# AFE4220.net
KiCad netlist of a schematic drawn in Altium Designer
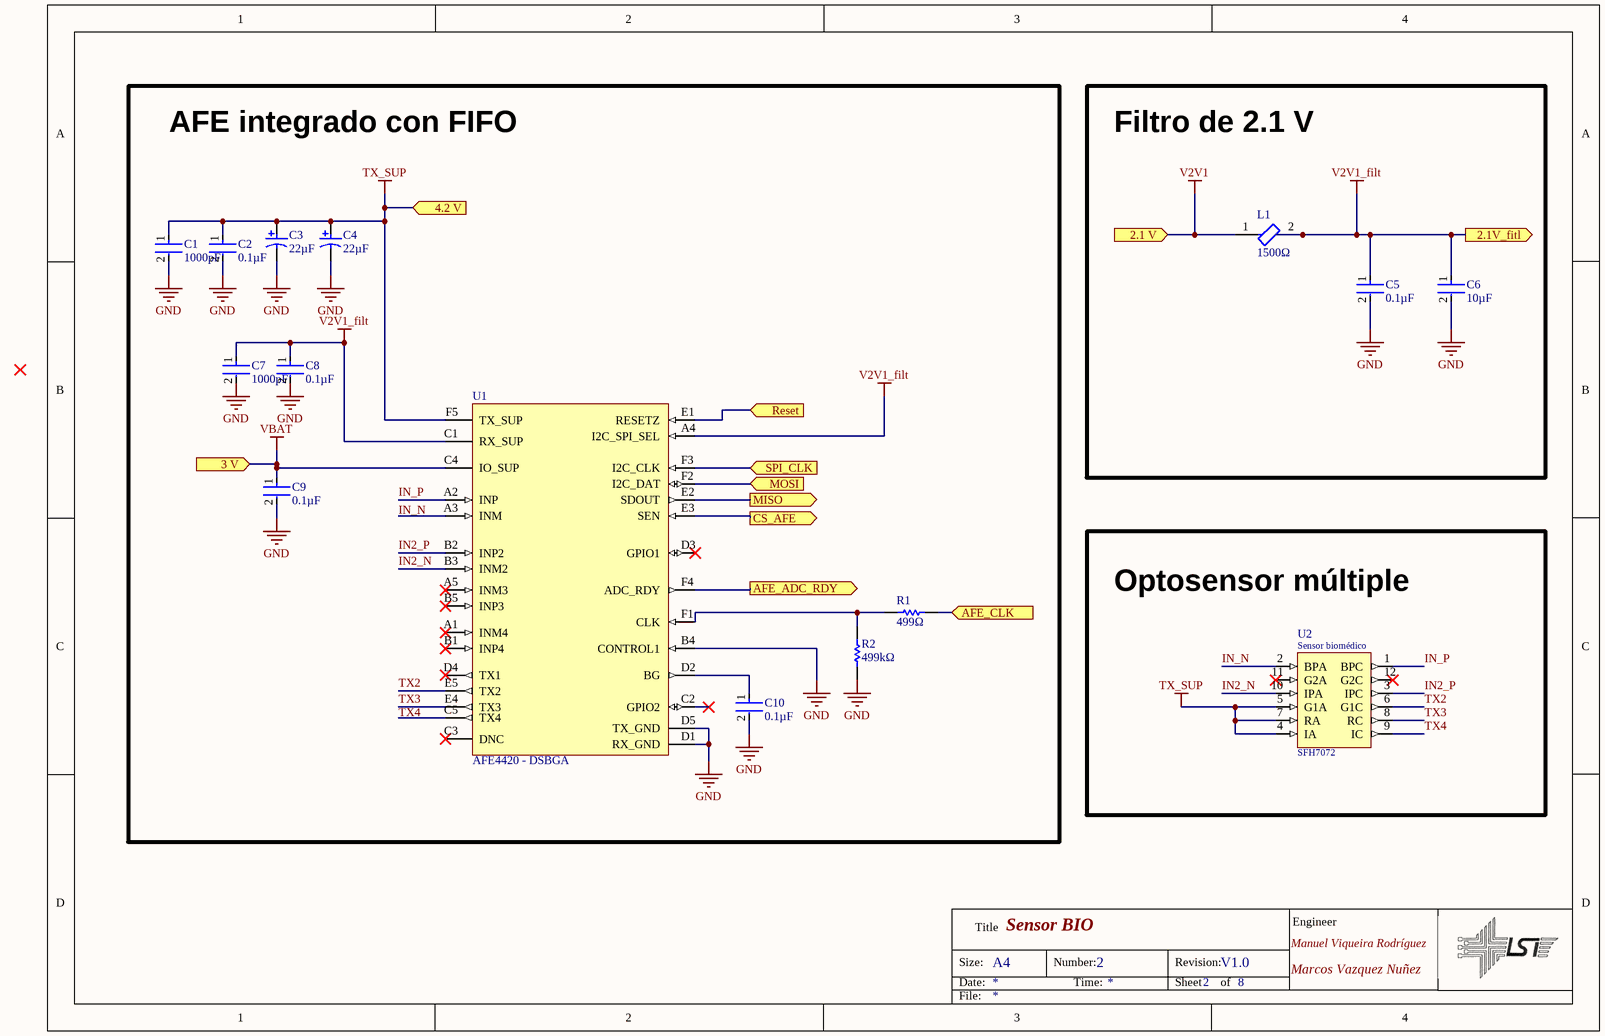
[diagram p0: AFE4220.SchDoc]

(export (version "E")
  (design (tool "Eeschema 10.0.6"))
  (components
    (comp (ref "C1")
      (value "1000pF")
      (footprint "FP-CL10-IPC_B")
      (description "Cap Ceramic 10uF 10V X5R ±10% Pad SMD 0603 +85°C T/R")
      (fields (field (name "TOLERANCE") "10%"))
      (libsource (lib "Altium Content Vault") (part "b4654b650e69147ec39a6b967a45e02"))
    )
    (comp (ref "C2")
      (value "0.1µF")
      (footprint "FP-CL10-IPC_B")
      (description "Cap Ceramic 10uF 10V X5R ±10% Pad SMD 0603 +85°C T/R")
      (fields (field (name "TOLERANCE") "10%"))
      (libsource (lib "Altium Content Vault") (part "b4654b650e69147ec39a6b967a45e02"))
    )
    (comp (ref "C3")
      (value "22µF")
      (footprint "NIC-CAPA2-4X5.8_V")
      (fields (field (name "MANUFACTURER") "Nichicon") (field (name "PARTNUMBER") "UUD1A220MCL1GS"))
      (libsource (lib "Altium Content Vault") (part "NIC-CAP-P-2"))
    )
    (comp (ref "C4")
      (value "22µF")
      (footprint "NIC-CAPA2-4X5.8_V")
      (fields (field (name "MANUFACTURER") "Nichicon") (field (name "PARTNUMBER") "UUD1A220MCL1GS"))
      (libsource (lib "Altium Content Vault") (part "NIC-CAP-P-2"))
    )
    (comp (ref "C5")
      (value "0.1µF")
      (footprint "FP-CL10-IPC_B")
      (description "Cap Ceramic 10uF 10V X5R ±10% Pad SMD 0603 +85°C T/R")
      (fields (field (name "TOLERANCE") "10%"))
      (libsource (lib "Altium Content Vault") (part "b4654b650e69147ec39a6b967a45e02"))
    )
    (comp (ref "C6")
      (value "10µF")
      (footprint "FP-CL10-IPC_B")
      (description "Cap Ceramic 10uF 10V X5R ±10% Pad SMD 0603 +85°C T/R")
      (fields (field (name "TOLERANCE") "10%"))
      (libsource (lib "Altium Content Vault") (part "b4654b650e69147ec39a6b967a45e02"))
    )
    (comp (ref "C7")
      (value "1000pF")
      (footprint "FP-CL10-IPC_B")
      (description "Cap Ceramic 10uF 10V X5R ±10% Pad SMD 0603 +85°C T/R")
      (fields (field (name "TOLERANCE") "10%"))
      (libsource (lib "Altium Content Vault") (part "b4654b650e69147ec39a6b967a45e02"))
    )
    (comp (ref "C8")
      (value "0.1µF")
      (footprint "FP-CL10-IPC_B")
      (description "Cap Ceramic 10uF 10V X5R ±10% Pad SMD 0603 +85°C T/R")
      (fields (field (name "TOLERANCE") "10%"))
      (libsource (lib "Altium Content Vault") (part "b4654b650e69147ec39a6b967a45e02"))
    )
    (comp (ref "C9")
      (value "0.1µF")
      (footprint "FP-CL10-IPC_B")
      (description "Cap Ceramic 10uF 10V X5R ±10% Pad SMD 0603 +85°C T/R")
      (fields (field (name "TOLERANCE") "10%"))
      (libsource (lib "Altium Content Vault") (part "b4654b650e69147ec39a6b967a45e02"))
    )
    (comp (ref "C10")
      (value "0.1µF")
      (footprint "FP-CL10-IPC_B")
      (description "Cap Ceramic 10uF 10V X5R ±10% Pad SMD 0603 +85°C T/R")
      (fields (field (name "TOLERANCE") "10%"))
      (libsource (lib "Altium Content Vault") (part "b4654b650e69147ec39a6b967a45e02"))
    )
    (comp (ref "L1")
      (value "1500Ω")
      (footprint "FP-BLM18-0_15-t0_8-IPC_C")
      (description "Chip Ferrite Bead, 0603, 1500Ω @ 100MHz, 0.5Ω, 25%, 500mA")
      (fields (field (name "TOLERANCE") "25%"))
      (libsource (lib "Altium Content Vault") (part "5f30dd21d616792df468990f7003faa"))
    )
    (comp (ref "R1")
      (value "499Ω")
      (footprint "RESC0603X28X15ML05T05")
      (fields (field (name "MANUFACTURER") "Vishay Dale") (field (name "PART NUMBER") "CRCW020120K0JNED"))
      (libsource (lib "Altium Content Vault") (part "RES"))
    )
    (comp (ref "R2")
      (value "499kΩ")
      (footprint "RESC0603X28X15ML05T05")
      (fields (field (name "MANUFACTURER") "Vishay Dale") (field (name "PART NUMBER") "CRCW020120K0JNED"))
      (libsource (lib "Altium Content Vault") (part "RES"))
    )
    (comp (ref "U1")
      (value "AFE4420 - DSBGA")
      (footprint "AFE4420 - DSBGA")
      (libsource (lib "DEOP2021") (part "AFE4420 - DSBGA"))
    )
    (comp (ref "U2")
      (value "~")
      (footprint "SFH7072")
      (description "Sensor biométrico")
      (libsource (lib "DEOP2021") (part "SFH7072"))
    )
  )
  (nets
    (net (code "1") (name "/AFE_ADC_RDY") (class "Default")
      (node (ref "U1") (pin "F4") (pinfunction "ADC_RDY_F4") (pintype "output"))
    )
    (net (code "2") (name "/AFE_CLK") (class "Default")
      (node (ref "R1") (pin "2") (pinfunction "2_2") (pintype "passive"))
    )
    (net (code "3") (name "/CS_AFE") (class "Default")
      (node (ref "U1") (pin "E3") (pinfunction "SEN_E3") (pintype "input"))
    )
    (net (code "4") (name "/IN2_N") (class "Default")
      (node (ref "U1") (pin "B3") (pinfunction "INM2_B3") (pintype "input"))
      (node (ref "U2") (pin "10") (pinfunction "IPA_10") (pintype "input"))
    )
    (net (code "5") (name "/IN2_P") (class "Default")
      (node (ref "U1") (pin "B2") (pinfunction "INP2_B2") (pintype "input"))
      (node (ref "U2") (pin "3") (pinfunction "IPC_3") (pintype "output"))
    )
    (net (code "6") (name "/IN_N") (class "Default")
      (node (ref "U2") (pin "2") (pinfunction "BPA_2") (pintype "input"))
    )
    (net (code "7") (name "/IN_P") (class "Default")
      (node (ref "U1") (pin "A2") (pinfunction "INP_A2") (pintype "input"))
      (node (ref "U2") (pin "1") (pinfunction "BPC_1") (pintype "output"))
    )
    (net (code "8") (name "/MISO") (class "Default")
      (node (ref "U1") (pin "E2") (pinfunction "SDOUT_E2") (pintype "output"))
    )
    (net (code "9") (name "/MOSI") (class "Default")
      (node (ref "U1") (pin "F2") (pinfunction "I2C_DAT_F2") (pintype "bidirectional"))
    )
    (net (code "10") (name "/Reset") (class "Default")
      (node (ref "U1") (pin "E1") (pinfunction "RESETZ_E1") (pintype "input"))
    )
    (net (code "11") (name "/SPI_CLK") (class "Default")
      (node (ref "U1") (pin "F3") (pinfunction "I2C_CLK_F3") (pintype "input"))
    )
    (net (code "12") (name "/TX2") (class "Default")
      (node (ref "U1") (pin "E5") (pinfunction "TX2_E5") (pintype "output"))
      (node (ref "U2") (pin "6") (pinfunction "G1C_6") (pintype "output"))
    )
    (net (code "13") (name "/TX3") (class "Default")
      (node (ref "U1") (pin "E4") (pinfunction "TX3_E4") (pintype "output"))
      (node (ref "U2") (pin "8") (pinfunction "RC_8") (pintype "output"))
    )
    (net (code "14") (name "/TX4") (class "Default")
      (node (ref "U2") (pin "9") (pinfunction "IC_9") (pintype "output"))
    )
    (net (code "15") (name "GND") (class "Default")
      (node (ref "C1") (pin "2") (pinfunction "2_2") (pintype "passive"))
      (node (ref "C10") (pin "2") (pinfunction "2_2") (pintype "passive"))
      (node (ref "C2") (pin "2") (pinfunction "2_2") (pintype "passive"))
      (node (ref "C3") (pin "2") (pinfunction "2_2") (pintype "passive"))
      (node (ref "C4") (pin "2") (pinfunction "2_2") (pintype "passive"))
      (node (ref "C5") (pin "2") (pinfunction "2_2") (pintype "passive"))
      (node (ref "C6") (pin "2") (pinfunction "2_2") (pintype "passive"))
      (node (ref "C7") (pin "2") (pinfunction "2_2") (pintype "passive"))
      (node (ref "C8") (pin "2") (pinfunction "2_2") (pintype "passive"))
      (node (ref "C9") (pin "2") (pinfunction "2_2") (pintype "passive"))
      (node (ref "R2") (pin "1") (pinfunction "1_1") (pintype "passive"))
      (node (ref "U1") (pin "B4") (pinfunction "CONTROL1_B4") (pintype "input"))
      (node (ref "U1") (pin "D1") (pinfunction "RX_GND_D1") (pintype "power_in"))
      (node (ref "U1") (pin "D5") (pinfunction "TX_GND_D5") (pintype "power_in"))
    )
    (net (code "16") (name "Net-(U1-BG)") (class "Default")
      (node (ref "C10") (pin "1") (pinfunction "1_1") (pintype "passive"))
      (node (ref "U1") (pin "D2") (pinfunction "BG_D2") (pintype "output"))
    )
    (net (code "17") (name "Net-(U1-CLK)") (class "Default")
      (node (ref "R1") (pin "1") (pinfunction "1_1") (pintype "passive"))
      (node (ref "R2") (pin "2") (pinfunction "2_2") (pintype "passive"))
      (node (ref "U1") (pin "F1") (pinfunction "CLK_F1") (pintype "input"))
    )
    (net (code "18") (name "TX_SUP") (class "Default")
      (node (ref "C1") (pin "1") (pinfunction "1_1") (pintype "passive"))
      (node (ref "C2") (pin "1") (pinfunction "1_1") (pintype "passive"))
      (node (ref "C3") (pin "1") (pinfunction "1_1") (pintype "passive"))
      (node (ref "C4") (pin "1") (pinfunction "1_1") (pintype "passive"))
      (node (ref "U1") (pin "F5") (pinfunction "TX_SUP_F5") (pintype "power_in"))
      (node (ref "U2") (pin "4") (pinfunction "IA_4") (pintype "input"))
      (node (ref "U2") (pin "5") (pinfunction "G1A_5") (pintype "input"))
      (node (ref "U2") (pin "7") (pinfunction "RA_7") (pintype "input"))
    )
    (net (code "19") (name "V2V1") (class "Default")
      (node (ref "L1") (pin "1") (pinfunction "1_1") (pintype "passive"))
    )
    (net (code "20") (name "V2V1_filt") (class "Default")
      (node (ref "C5") (pin "1") (pinfunction "1_1") (pintype "passive"))
      (node (ref "C6") (pin "1") (pinfunction "1_1") (pintype "passive"))
      (node (ref "C7") (pin "1") (pinfunction "1_1") (pintype "passive"))
      (node (ref "C8") (pin "1") (pinfunction "1_1") (pintype "passive"))
      (node (ref "L1") (pin "2") (pinfunction "2_2") (pintype "passive"))
      (node (ref "U1") (pin "A4") (pinfunction "I2C_SPI_SEL_A4") (pintype "input"))
      (node (ref "U1") (pin "C1") (pinfunction "RX_SUP_C1") (pintype "power_in"))
    )
    (net (code "21") (name "VBAT") (class "Default")
      (node (ref "C9") (pin "1") (pinfunction "1_1") (pintype "passive"))
      (node (ref "U1") (pin "C4") (pinfunction "IO_SUP_C4") (pintype "power_in"))
    )
    (net (code "22") (name "unconnected-(U1-DNC-PadC3)") (class "Default")
      (node (ref "U1") (pin "C3") (pinfunction "DNC_C3") (pintype "passive+no_connect"))
    )
    (net (code "23") (name "unconnected-(U1-GPIO1-PadD3)") (class "Default")
      (node (ref "U1") (pin "D3") (pinfunction "GPIO1_D3") (pintype "bidirectional+no_connect"))
    )
    (net (code "24") (name "unconnected-(U1-GPIO2-PadC2)") (class "Default")
      (node (ref "U1") (pin "C2") (pinfunction "GPIO2_C2") (pintype "bidirectional+no_connect"))
    )
    (net (code "25") (name "unconnected-(U1-INM-PadA3)") (class "Default")
      (node (ref "U1") (pin "A3") (pinfunction "INM_A3") (pintype "input"))
    )
    (net (code "26") (name "unconnected-(U1-INM3-PadA5)") (class "Default")
      (node (ref "U1") (pin "A5") (pinfunction "INM3_A5") (pintype "input+no_connect"))
    )
    (net (code "27") (name "unconnected-(U1-INM4-PadA1)") (class "Default")
      (node (ref "U1") (pin "A1") (pinfunction "INM4_A1") (pintype "input+no_connect"))
    )
    (net (code "28") (name "unconnected-(U1-INP3-PadB5)") (class "Default")
      (node (ref "U1") (pin "B5") (pinfunction "INP3_B5") (pintype "input+no_connect"))
    )
    (net (code "29") (name "unconnected-(U1-INP4-PadB1)") (class "Default")
      (node (ref "U1") (pin "B1") (pinfunction "INP4_B1") (pintype "input+no_connect"))
    )
    (net (code "30") (name "unconnected-(U1-TX1-PadD4)") (class "Default")
      (node (ref "U1") (pin "D4") (pinfunction "TX1_D4") (pintype "output+no_connect"))
    )
    (net (code "31") (name "unconnected-(U1-TX4-PadC5)") (class "Default")
      (node (ref "U1") (pin "C5") (pinfunction "TX4_C5") (pintype "output"))
    )
    (net (code "32") (name "unconnected-(U2-G2A-Pad11)") (class "Default")
      (node (ref "U2") (pin "11") (pinfunction "G2A_11") (pintype "input+no_connect"))
    )
    (net (code "33") (name "unconnected-(U2-G2C-Pad12)") (class "Default")
      (node (ref "U2") (pin "12") (pinfunction "G2C_12") (pintype "output+no_connect"))
    )
  )
)
